# PiZeroGeiger_REV_A.net
KiCad netlist of a schematic drawn in EAGLE
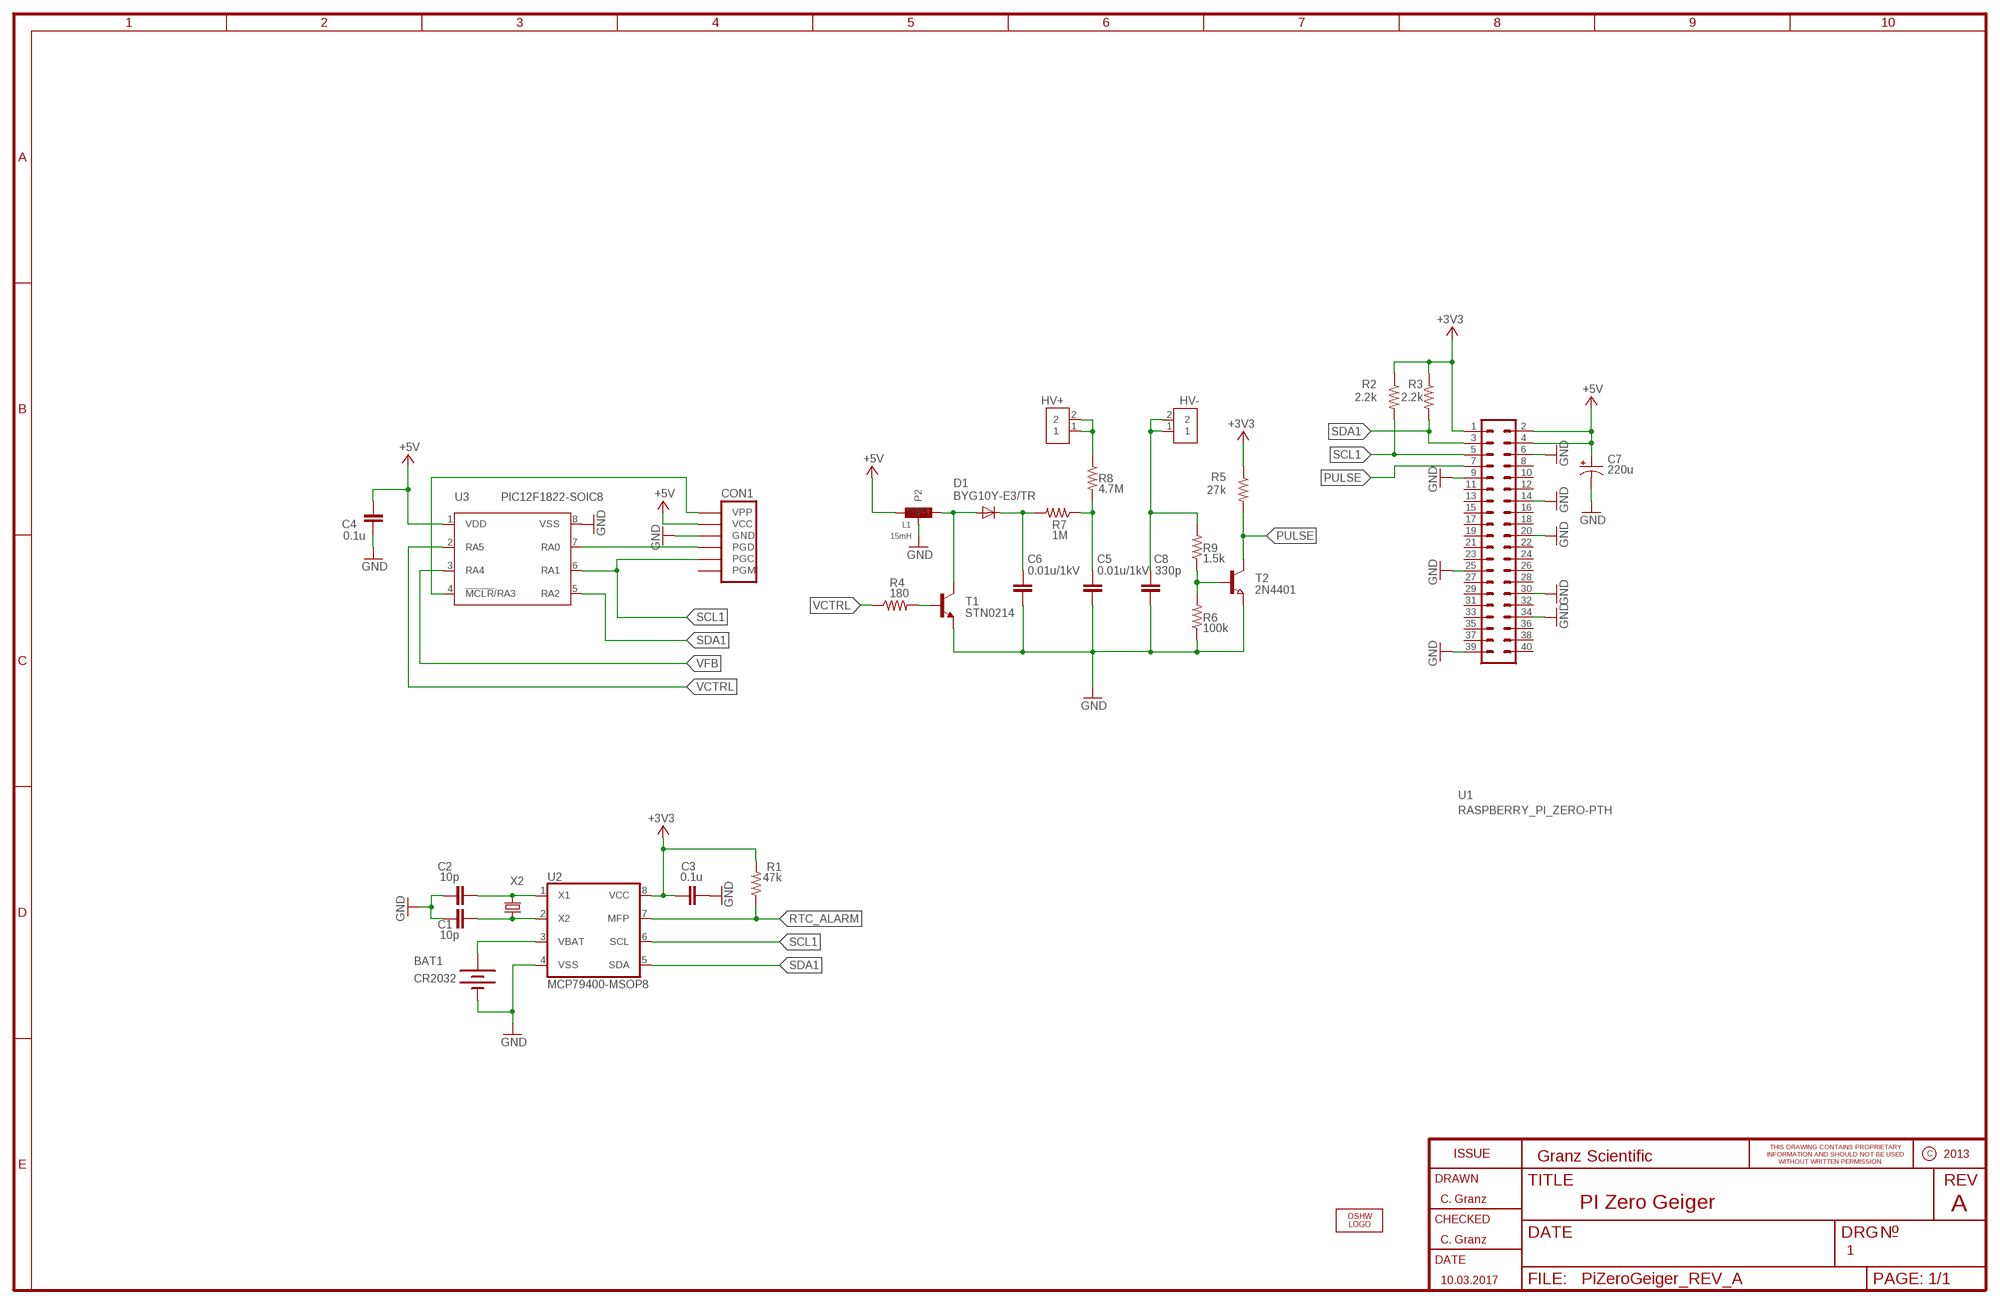
[diagram p0: schematic, sheet 1]

(export (version "E")
  (design (tool "Eeschema 10.0.6"))
  (components
    (comp (ref "BAT1")
      (value "CR2032")
      (footprint "eagle-import:BATTERY_HOLDER_12MM_BK-885")
      (libsource (lib "eagle-import") (part "BATTERY-BK-885"))
    )
    (comp (ref "C1")
      (value "10p")
      (footprint "eagle-import:RCL_0805")
      (libsource (lib "eagle-import") (part "CAPACITOR-0805"))
    )
    (comp (ref "C2")
      (value "10p")
      (footprint "eagle-import:RCL_0805")
      (libsource (lib "eagle-import") (part "CAPACITOR-0805"))
    )
    (comp (ref "C3")
      (value "0.1u")
      (footprint "eagle-import:RCL_0805")
      (libsource (lib "eagle-import") (part "CAPACITOR-0805"))
    )
    (comp (ref "C4")
      (value "0.1u")
      (footprint "eagle-import:RCL_0805")
      (fields (field (name "EAGLEUP") "C0805"))
      (libsource (lib "eagle-import") (part "CGranz_CAPACITOR-0805"))
    )
    (comp (ref "C5")
      (value "0.01u/1kV")
      (footprint "eagle-import:RCL_1812")
      (libsource (lib "eagle-import") (part "CAPACITOR-1812"))
    )
    (comp (ref "C6")
      (value "0.01u/1kV")
      (footprint "eagle-import:RCL_1812")
      (libsource (lib "eagle-import") (part "CAPACITOR-1812"))
    )
    (comp (ref "C7")
      (value "220u")
      (footprint "eagle-import:CAPACITOR_POLARIZED_PTH_2.5MM-7MM")
      (libsource (lib "eagle-import") (part "CAPACITOR_POLARIZED-PTH-2.5MM-7MM"))
    )
    (comp (ref "C8")
      (value "330p")
      (footprint "eagle-import:RCL_0805")
      (libsource (lib "eagle-import") (part "CGranz_CAPACITOR-0805"))
    )
    (comp (ref "CON1")
      (value "CON_PIC_ICSP")
      (footprint "eagle-import:CON_INLINE_TE_640456-6")
      (libsource (lib "eagle-import") (part "CON_PIC_ICSP"))
    )
    (comp (ref "D1")
      (value "BYG10Y-E3/TR")
      (footprint "eagle-import:DO-214AC")
      (libsource (lib "eagle-import") (part "DIODE-DO-214AC"))
    )
    (comp (ref "HV+")
      (value "FUSE_HOLDER-PTH")
      (footprint "eagle-import:FUSE_HOLDER_PTH")
      (libsource (lib "eagle-import") (part "FUSE_HOLDER-PTH"))
    )
    (comp (ref "HV-")
      (value "FUSE_HOLDER-PTH")
      (footprint "eagle-import:FUSE_HOLDER_PTH")
      (libsource (lib "eagle-import") (part "FUSE_HOLDER-PTH"))
    )
    (comp (ref "L1")
      (value "15mH")
      (footprint "eagle-import:1200LRS")
      (libsource (lib "eagle-import") (part "1200LRS"))
    )
    (comp (ref "LOGO1")
      (value "OSHW_LOGO_FILLX0150-NT")
      (footprint "eagle-import:OSHW_FILLX150_NOTEXT")
      (libsource (lib "eagle-import") (part "OSHW_LOGO_FILLX0150-NT"))
    )
    (comp (ref "R1")
      (value "47k")
      (footprint "eagle-import:RCL_0805")
      (libsource (lib "eagle-import") (part "RESISTOR-0805"))
    )
    (comp (ref "R2")
      (value "2.2k")
      (footprint "eagle-import:RCL_0805")
      (fields (field (name "EAGLEUP") "R0805"))
      (libsource (lib "eagle-import") (part "CGranz_RESISTOR-0805"))
    )
    (comp (ref "R3")
      (value "2.2k")
      (footprint "eagle-import:RCL_0805")
      (fields (field (name "EAGLEUP") "R0805"))
      (libsource (lib "eagle-import") (part "CGranz_RESISTOR-0805"))
    )
    (comp (ref "R4")
      (value "180")
      (footprint "eagle-import:RCL_0805")
      (libsource (lib "eagle-import") (part "CGranz_RESISTOR-0805"))
    )
    (comp (ref "R5")
      (value "27k")
      (footprint "eagle-import:RCL_0805")
      (libsource (lib "eagle-import") (part "CGranz_RESISTOR-0805"))
    )
    (comp (ref "R6")
      (value "100k")
      (footprint "eagle-import:RCL_0805")
      (libsource (lib "eagle-import") (part "CGranz_RESISTOR-0805"))
    )
    (comp (ref "R7")
      (value "1M")
      (footprint "eagle-import:RCL_0805")
      (libsource (lib "eagle-import") (part "CGranz_RESISTOR-0805"))
    )
    (comp (ref "R8")
      (value "4.7M")
      (footprint "eagle-import:RCL_0805")
      (libsource (lib "eagle-import") (part "CGranz_RESISTOR-0805"))
    )
    (comp (ref "R9")
      (value "1.5k")
      (footprint "eagle-import:RCL_0805")
      (libsource (lib "eagle-import") (part "CGranz_RESISTOR-0805"))
    )
    (comp (ref "T1")
      (value "STN0214")
      (footprint "eagle-import:SOT223")
      (libsource (lib "eagle-import") (part "-NPN-SOT223"))
    )
    (comp (ref "T2")
      (value "2N4401")
      (footprint "eagle-import:SOT23")
      (libsource (lib "eagle-import") (part "NPN-TRANSISTOR_SOT23"))
    )
    (comp (ref "U1")
      (value "RASPBERRY_PI_ZERO-PTH")
      (footprint "eagle-import:RASPBERRY_PI_ZERO")
      (libsource (lib "eagle-import") (part "RASPBERRY_PI_ZERO-PTH"))
    )
    (comp (ref "U2")
      (value "MCP79400-MSOP8")
      (footprint "eagle-import:MSOP8")
      (fields (field (name "PN") "MCP79400-I/SN"))
      (libsource (lib "eagle-import") (part "MCP79400-MSOP8"))
    )
    (comp (ref "U3")
      (value "PIC12F1822-SOIC8")
      (footprint "eagle-import:SOIC8")
      (libsource (lib "eagle-import") (part "PIC12F1822-SOIC8"))
    )
    (comp (ref "X2")
      (value "32.768 kHz 12.5 pF X1123-ND")
      (footprint "eagle-import:CRYSTAL_ABRACON_ABS10")
      (fields (field (name "PN") "ABS10-32.768KHZ-1-T"))
      (libsource (lib "eagle-import") (part "CRYSTAL_2_PIN-4.9MM_X_1.8MM"))
    )
  )
  (nets
    (net (code "1") (name "+3V3") (class "Default")
      (node (ref "C3") (pin "2") (pinfunction "2_2") (pintype "passive"))
      (node (ref "R1") (pin "2") (pinfunction "2_2") (pintype "passive"))
      (node (ref "R2") (pin "1") (pinfunction "1_1") (pintype "passive"))
      (node (ref "R3") (pin "1") (pinfunction "1_1") (pintype "passive"))
      (node (ref "R5") (pin "1") (pinfunction "1_1") (pintype "passive"))
      (node (ref "U1") (pin "1") (pinfunction "1_1") (pintype "passive"))
      (node (ref "U2") (pin "8") (pinfunction "VCC_8") (pintype "power_in"))
    )
    (net (code "2") (name "+5V") (class "Default")
      (node (ref "C4") (pin "1") (pinfunction "1_1") (pintype "passive"))
      (node (ref "C7") (pin "+") (pinfunction "+_+") (pintype "passive"))
      (node (ref "CON1") (pin "5") (pinfunction "VCC_5") (pintype "passive"))
      (node (ref "L1") (pin "P1") (pinfunction "P1_P1") (pintype "bidirectional"))
      (node (ref "U1") (pin "2") (pinfunction "2_2") (pintype "passive"))
      (node (ref "U1") (pin "4") (pinfunction "4_4") (pintype "passive"))
      (node (ref "U3") (pin "1") (pinfunction "VDD_1") (pintype "power_in"))
    )
    (net (code "3") (name "GND") (class "Default")
      (node (ref "BAT1") (pin "-") (pinfunction "-_-") (pintype "power_in"))
      (node (ref "C1") (pin "2") (pinfunction "2_2") (pintype "passive"))
      (node (ref "C2") (pin "2") (pinfunction "2_2") (pintype "passive"))
      (node (ref "C3") (pin "1") (pinfunction "1_1") (pintype "passive"))
      (node (ref "C4") (pin "2") (pinfunction "2_2") (pintype "passive"))
      (node (ref "C5") (pin "2") (pinfunction "2_2") (pintype "passive"))
      (node (ref "C6") (pin "2") (pinfunction "2_2") (pintype "passive"))
      (node (ref "C7") (pin "-") (pinfunction "-_-") (pintype "passive"))
      (node (ref "C8") (pin "2") (pinfunction "2_2") (pintype "passive"))
      (node (ref "CON1") (pin "4") (pinfunction "GND_4") (pintype "passive"))
      (node (ref "L1") (pin "P4") (pinfunction "P2_P4") (pintype "bidirectional"))
      (node (ref "R6") (pin "1") (pinfunction "1_1") (pintype "passive"))
      (node (ref "T1") (pin "3") (pinfunction "E_3") (pintype "passive"))
      (node (ref "T2") (pin "2") (pinfunction "E_2") (pintype "passive"))
      (node (ref "U1") (pin "14") (pinfunction "14_14") (pintype "passive"))
      (node (ref "U1") (pin "20") (pinfunction "20_20") (pintype "passive"))
      (node (ref "U1") (pin "25") (pinfunction "25_25") (pintype "passive"))
      (node (ref "U1") (pin "30") (pinfunction "30_30") (pintype "passive"))
      (node (ref "U1") (pin "34") (pinfunction "34_34") (pintype "passive"))
      (node (ref "U1") (pin "39") (pinfunction "39_39") (pintype "passive"))
      (node (ref "U1") (pin "6") (pinfunction "6_6") (pintype "passive"))
      (node (ref "U1") (pin "9") (pinfunction "9_9") (pintype "passive"))
      (node (ref "U2") (pin "4") (pinfunction "VSS_4") (pintype "power_in"))
      (node (ref "U3") (pin "8") (pinfunction "VSS_8") (pintype "power_in"))
    )
    (net (code "4") (name "Net-(BAT1-+)") (class "Default")
      (node (ref "BAT1") (pin "+A") (pinfunction "+_+A") (pintype "power_in"))
      (node (ref "U2") (pin "3") (pinfunction "VBAT_3") (pintype "power_in"))
    )
    (net (code "5") (name "Net-(C5-Pad1)") (class "Default")
      (node (ref "C5") (pin "1") (pinfunction "1_1") (pintype "passive"))
      (node (ref "R7") (pin "1") (pinfunction "1_1") (pintype "passive"))
      (node (ref "R8") (pin "2") (pinfunction "2_2") (pintype "passive"))
    )
    (net (code "6") (name "Net-(C6-Pad1)") (class "Default")
      (node (ref "C6") (pin "1") (pinfunction "1_1") (pintype "passive"))
      (node (ref "D1") (pin "C") (pinfunction "C_C") (pintype "passive"))
      (node (ref "R7") (pin "2") (pinfunction "2_2") (pintype "passive"))
    )
    (net (code "7") (name "Net-(C8-Pad1)") (class "Default")
      (node (ref "C8") (pin "1") (pinfunction "1_1") (pintype "passive"))
      (node (ref "HV-") (pin "1") (pinfunction "1_1") (pintype "passive"))
      (node (ref "HV-") (pin "2") (pinfunction "2_2") (pintype "passive"))
      (node (ref "R9") (pin "2") (pinfunction "2_2") (pintype "passive"))
    )
    (net (code "8") (name "Net-(CON1-PGD)") (class "Default")
      (node (ref "CON1") (pin "3") (pinfunction "PGD_3") (pintype "passive"))
      (node (ref "U3") (pin "7") (pinfunction "RA0_7") (pintype "bidirectional"))
    )
    (net (code "9") (name "Net-(CON1-VPP)") (class "Default")
      (node (ref "CON1") (pin "6") (pinfunction "VPP_6") (pintype "passive"))
      (node (ref "U3") (pin "4") (pinfunction "~{MCLR}/RA3_4") (pintype "bidirectional"))
    )
    (net (code "10") (name "Net-(HV+-Pad1)") (class "Default")
      (node (ref "HV+") (pin "1") (pinfunction "1_1") (pintype "passive"))
      (node (ref "HV+") (pin "2") (pinfunction "2_2") (pintype "passive"))
      (node (ref "R8") (pin "1") (pinfunction "1_1") (pintype "passive"))
    )
    (net (code "11") (name "Net-(T1-B)") (class "Default")
      (node (ref "R4") (pin "2") (pinfunction "2_2") (pintype "passive"))
      (node (ref "T1") (pin "1") (pinfunction "B_1") (pintype "passive"))
    )
    (net (code "12") (name "Net-(T1-C)") (class "Default")
      (node (ref "D1") (pin "A") (pinfunction "A_A") (pintype "passive"))
      (node (ref "L1") (pin "P3") (pinfunction "P3_P3") (pintype "bidirectional"))
      (node (ref "T1") (pin "4") (pinfunction "C_4") (pintype "passive"))
    )
    (net (code "13") (name "Net-(T2-B)") (class "Default")
      (node (ref "R6") (pin "2") (pinfunction "2_2") (pintype "passive"))
      (node (ref "R9") (pin "1") (pinfunction "1_1") (pintype "passive"))
      (node (ref "T2") (pin "1") (pinfunction "B_1") (pintype "passive"))
    )
    (net (code "14") (name "Net-(U2-X1)") (class "Default")
      (node (ref "C2") (pin "1") (pinfunction "1_1") (pintype "passive"))
      (node (ref "U2") (pin "1") (pinfunction "X1_1") (pintype "passive"))
      (node (ref "X2") (pin "2") (pinfunction "2_2") (pintype "passive"))
    )
    (net (code "15") (name "Net-(U2-X2)") (class "Default")
      (node (ref "C1") (pin "1") (pinfunction "1_1") (pintype "passive"))
      (node (ref "U2") (pin "2") (pinfunction "X2_2") (pintype "passive"))
      (node (ref "X2") (pin "1") (pinfunction "1_1") (pintype "passive"))
    )
    (net (code "16") (name "PULSE") (class "Default")
      (node (ref "R5") (pin "2") (pinfunction "2_2") (pintype "passive"))
      (node (ref "T2") (pin "3") (pinfunction "C_3") (pintype "passive"))
      (node (ref "U1") (pin "7") (pinfunction "7_7") (pintype "passive"))
    )
    (net (code "17") (name "RTC_ALARM") (class "Default")
      (node (ref "R1") (pin "1") (pinfunction "1_1") (pintype "passive"))
      (node (ref "U2") (pin "7") (pinfunction "MFP_7") (pintype "output"))
    )
    (net (code "18") (name "SCL1") (class "Default")
      (node (ref "CON1") (pin "2") (pinfunction "PGC_2") (pintype "passive"))
      (node (ref "R2") (pin "2") (pinfunction "2_2") (pintype "passive"))
      (node (ref "U1") (pin "5") (pinfunction "5_5") (pintype "passive"))
      (node (ref "U2") (pin "6") (pinfunction "SCL_6") (pintype "input"))
      (node (ref "U3") (pin "6") (pinfunction "RA1_6") (pintype "bidirectional"))
    )
    (net (code "19") (name "SDA1") (class "Default")
      (node (ref "R3") (pin "2") (pinfunction "2_2") (pintype "passive"))
      (node (ref "U1") (pin "3") (pinfunction "3_3") (pintype "passive"))
      (node (ref "U2") (pin "5") (pinfunction "SDA_5") (pintype "bidirectional"))
      (node (ref "U3") (pin "5") (pinfunction "RA2_5") (pintype "bidirectional"))
    )
    (net (code "20") (name "VCTRL") (class "Default")
      (node (ref "R4") (pin "1") (pinfunction "1_1") (pintype "passive"))
      (node (ref "U3") (pin "2") (pinfunction "RA5_2") (pintype "bidirectional"))
    )
    (net (code "21") (name "VFB") (class "Default")
      (node (ref "U3") (pin "3") (pinfunction "RA4_3") (pintype "bidirectional"))
    )
    (net (code "22") (name "unconnected-(CON1-PGM-Pad1)") (class "Default")
      (node (ref "CON1") (pin "1") (pinfunction "PGM_1") (pintype "passive"))
    )
    (net (code "23") (name "unconnected-(U1-Pad8)") (class "Default")
      (node (ref "U1") (pin "8") (pinfunction "8_8") (pintype "passive"))
    )
    (net (code "24") (name "unconnected-(U1-Pad10)") (class "Default")
      (node (ref "U1") (pin "10") (pinfunction "10_10") (pintype "passive"))
    )
    (net (code "25") (name "unconnected-(U1-Pad11)") (class "Default")
      (node (ref "U1") (pin "11") (pinfunction "11_11") (pintype "passive"))
    )
    (net (code "26") (name "unconnected-(U1-Pad12)") (class "Default")
      (node (ref "U1") (pin "12") (pinfunction "12_12") (pintype "passive"))
    )
    (net (code "27") (name "unconnected-(U1-Pad13)") (class "Default")
      (node (ref "U1") (pin "13") (pinfunction "13_13") (pintype "passive"))
    )
    (net (code "28") (name "unconnected-(U1-Pad15)") (class "Default")
      (node (ref "U1") (pin "15") (pinfunction "15_15") (pintype "passive"))
    )
    (net (code "29") (name "unconnected-(U1-Pad16)") (class "Default")
      (node (ref "U1") (pin "16") (pinfunction "16_16") (pintype "passive"))
    )
    (net (code "30") (name "unconnected-(U1-Pad17)") (class "Default")
      (node (ref "U1") (pin "17") (pinfunction "17_17") (pintype "passive"))
    )
    (net (code "31") (name "unconnected-(U1-Pad18)") (class "Default")
      (node (ref "U1") (pin "18") (pinfunction "18_18") (pintype "passive"))
    )
    (net (code "32") (name "unconnected-(U1-Pad19)") (class "Default")
      (node (ref "U1") (pin "19") (pinfunction "19_19") (pintype "passive"))
    )
    (net (code "33") (name "unconnected-(U1-Pad21)") (class "Default")
      (node (ref "U1") (pin "21") (pinfunction "21_21") (pintype "passive"))
    )
    (net (code "34") (name "unconnected-(U1-Pad22)") (class "Default")
      (node (ref "U1") (pin "22") (pinfunction "22_22") (pintype "passive"))
    )
    (net (code "35") (name "unconnected-(U1-Pad23)") (class "Default")
      (node (ref "U1") (pin "23") (pinfunction "23_23") (pintype "passive"))
    )
    (net (code "36") (name "unconnected-(U1-Pad24)") (class "Default")
      (node (ref "U1") (pin "24") (pinfunction "24_24") (pintype "passive"))
    )
    (net (code "37") (name "unconnected-(U1-Pad26)") (class "Default")
      (node (ref "U1") (pin "26") (pinfunction "26_26") (pintype "passive"))
    )
    (net (code "38") (name "unconnected-(U1-Pad27)") (class "Default")
      (node (ref "U1") (pin "27") (pinfunction "27_27") (pintype "passive"))
    )
    (net (code "39") (name "unconnected-(U1-Pad28)") (class "Default")
      (node (ref "U1") (pin "28") (pinfunction "28_28") (pintype "passive"))
    )
    (net (code "40") (name "unconnected-(U1-Pad29)") (class "Default")
      (node (ref "U1") (pin "29") (pinfunction "29_29") (pintype "passive"))
    )
    (net (code "41") (name "unconnected-(U1-Pad31)") (class "Default")
      (node (ref "U1") (pin "31") (pinfunction "31_31") (pintype "passive"))
    )
    (net (code "42") (name "unconnected-(U1-Pad32)") (class "Default")
      (node (ref "U1") (pin "32") (pinfunction "32_32") (pintype "passive"))
    )
    (net (code "43") (name "unconnected-(U1-Pad33)") (class "Default")
      (node (ref "U1") (pin "33") (pinfunction "33_33") (pintype "passive"))
    )
    (net (code "44") (name "unconnected-(U1-Pad35)") (class "Default")
      (node (ref "U1") (pin "35") (pinfunction "35_35") (pintype "passive"))
    )
    (net (code "45") (name "unconnected-(U1-Pad36)") (class "Default")
      (node (ref "U1") (pin "36") (pinfunction "36_36") (pintype "passive"))
    )
    (net (code "46") (name "unconnected-(U1-Pad37)") (class "Default")
      (node (ref "U1") (pin "37") (pinfunction "37_37") (pintype "passive"))
    )
    (net (code "47") (name "unconnected-(U1-Pad38)") (class "Default")
      (node (ref "U1") (pin "38") (pinfunction "38_38") (pintype "passive"))
    )
    (net (code "48") (name "unconnected-(U1-Pad40)") (class "Default")
      (node (ref "U1") (pin "40") (pinfunction "40_40") (pintype "passive"))
    )
  )
)
